# NitroxAnalyzer_v2.net
KiCad netlist of a schematic drawn in EAGLE
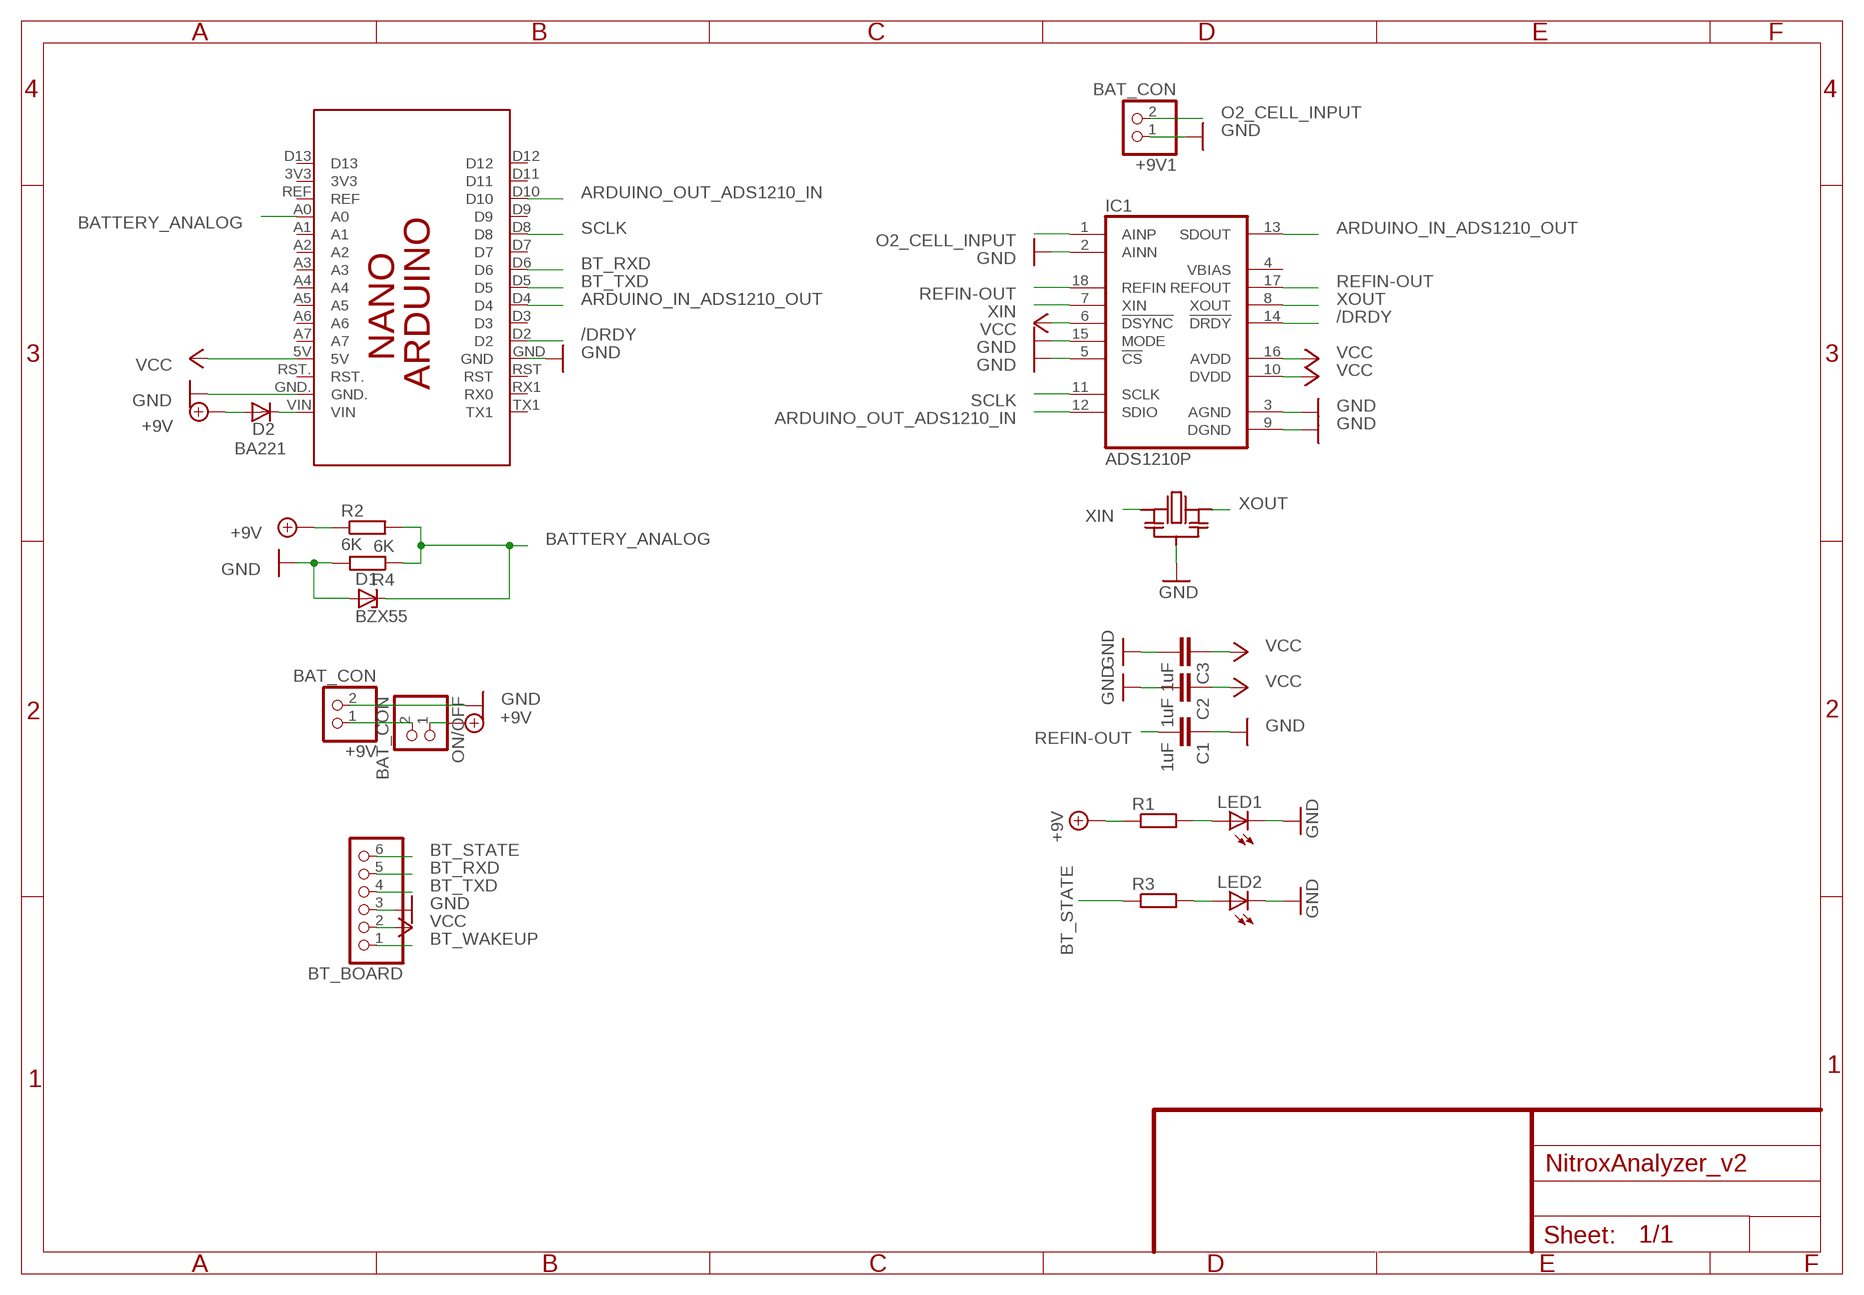
[diagram p0: schematic, sheet 1]

(export (version "E")
  (design (tool "Eeschema 10.0.6"))
  (components
    (comp (ref "+9V")
      (value "BAT_CON")
      (footprint "eagle-import:1X02")
      (libsource (lib "eagle-import") (part "PINHD-1X2"))
    )
    (comp (ref "+9V1")
      (value "BAT_CON")
      (footprint "eagle-import:1X02")
      (libsource (lib "eagle-import") (part "PINHD-1X2"))
    )
    (comp (ref "BT_BOARD")
      (value "PINHD-1X6")
      (footprint "eagle-import:1X06")
      (libsource (lib "eagle-import") (part "PINHD-1X6"))
    )
    (comp (ref "C1")
      (value "1uF")
      (footprint "eagle-import:C1206")
      (libsource (lib "eagle-import") (part "C-EUC1206"))
    )
    (comp (ref "C2")
      (value "1uF")
      (footprint "eagle-import:C1206")
      (libsource (lib "eagle-import") (part "C-EUC1206"))
    )
    (comp (ref "C3")
      (value "1uF")
      (footprint "eagle-import:C1206")
      (libsource (lib "eagle-import") (part "C-EUC1206"))
    )
    (comp (ref "D1")
      (value "BZX55")
      (footprint "eagle-import:DO35Z10")
      (libsource (lib "eagle-import") (part "BZX55"))
    )
    (comp (ref "D2")
      (value "BA221")
      (footprint "eagle-import:DO35-10")
      (libsource (lib "eagle-import") (part "BA221"))
    )
    (comp (ref "IC1")
      (value "ADS1210P")
      (footprint "eagle-import:DIL18")
      (libsource (lib "eagle-import") (part "ADS1210P"))
    )
    (comp (ref "LED1")
      (value "LED3MM")
      (footprint "eagle-import:LED3MM")
      (libsource (lib "eagle-import") (part "LED3MM"))
    )
    (comp (ref "LED2")
      (value "LED3MM")
      (footprint "eagle-import:LED3MM")
      (libsource (lib "eagle-import") (part "LED3MM"))
    )
    (comp (ref "ON/OFF")
      (value "BAT_CON")
      (footprint "eagle-import:1X02")
      (libsource (lib "eagle-import") (part "PINHD-1X2"))
    )
    (comp (ref "PCB1")
      (value "ARDUINO_NANO_SOCKET")
      (footprint "eagle-import:ARDUINO_NANO_SOCKET")
      (libsource (lib "eagle-import") (part "ARDUINO_NANO_SOCKET"))
    )
    (comp (ref "R1")
      (value "R-EU_R1206")
      (footprint "eagle-import:R1206")
      (libsource (lib "eagle-import") (part "R-EU_R1206"))
    )
    (comp (ref "R2")
      (value "6K")
      (footprint "eagle-import:R1206")
      (libsource (lib "eagle-import") (part "R-EU_R1206"))
    )
    (comp (ref "R3")
      (value "R-EU_R1206")
      (footprint "eagle-import:R1206")
      (libsource (lib "eagle-import") (part "R-EU_R1206"))
    )
    (comp (ref "R4")
      (value "6K")
      (footprint "eagle-import:R1206")
      (libsource (lib "eagle-import") (part "R-EU_R1206"))
    )
    (comp (ref "U$2")
      (value "RESONATOR")
      (footprint "eagle-import:RESONATOR")
      (libsource (lib "eagle-import") (part "RESONATOR"))
    )
  )
  (nets
    (net (code "1") (name "+9V") (class "Default")
      (node (ref "D2") (pin "A") (pinfunction "A_A") (pintype "passive"))
      (node (ref "ON/OFF") (pin "1") (pinfunction "1_1") (pintype "passive"))
      (node (ref "R1") (pin "1") (pinfunction "1_1") (pintype "passive"))
      (node (ref "R2") (pin "1") (pinfunction "1_1") (pintype "passive"))
    )
    (net (code "2") (name "/ARDUINO_IN_ADS1210_OUT") (class "Default")
      (node (ref "IC1") (pin "13") (pinfunction "SDOUT_13") (pintype "output"))
      (node (ref "PCB1") (pin "D4") (pinfunction "D4_D4") (pintype "bidirectional"))
    )
    (net (code "3") (name "/ARDUINO_OUT_ADS1210_IN") (class "Default")
      (node (ref "IC1") (pin "12") (pinfunction "SDIO_12") (pintype "bidirectional"))
      (node (ref "PCB1") (pin "D10") (pinfunction "D10_D10") (pintype "bidirectional"))
    )
    (net (code "4") (name "/BATTERY_ANALOG") (class "Default")
      (node (ref "D1") (pin "C") (pinfunction "C_C") (pintype "passive"))
      (node (ref "PCB1") (pin "A0") (pinfunction "A0_A0") (pintype "bidirectional"))
      (node (ref "R2") (pin "2") (pinfunction "2_2") (pintype "passive"))
      (node (ref "R4") (pin "1") (pinfunction "1_1") (pintype "passive"))
    )
    (net (code "5") (name "/BT_RXD") (class "Default")
      (node (ref "BT_BOARD") (pin "5") (pinfunction "5_5") (pintype "passive"))
      (node (ref "PCB1") (pin "D6") (pinfunction "D6_D6") (pintype "bidirectional"))
    )
    (net (code "6") (name "/BT_STATE") (class "Default")
      (node (ref "BT_BOARD") (pin "6") (pinfunction "6_6") (pintype "passive"))
      (node (ref "R3") (pin "1") (pinfunction "1_1") (pintype "passive"))
    )
    (net (code "7") (name "/BT_TXD") (class "Default")
      (node (ref "BT_BOARD") (pin "4") (pinfunction "4_4") (pintype "passive"))
      (node (ref "PCB1") (pin "D5") (pinfunction "D5_D5") (pintype "bidirectional"))
    )
    (net (code "8") (name "/BT_WAKEUP") (class "Default")
      (node (ref "BT_BOARD") (pin "1") (pinfunction "1_1") (pintype "passive"))
    )
    (net (code "9") (name "/O2_CELL_INPUT") (class "Default")
      (node (ref "+9V1") (pin "2") (pinfunction "2_2") (pintype "passive"))
      (node (ref "IC1") (pin "1") (pinfunction "AINP_1") (pintype "input"))
    )
    (net (code "10") (name "/REFIN-OUT") (class "Default")
      (node (ref "C1") (pin "2") (pinfunction "2_2") (pintype "passive"))
      (node (ref "IC1") (pin "17") (pinfunction "REFOUT_17") (pintype "output"))
      (node (ref "IC1") (pin "18") (pinfunction "REFIN_18") (pintype "input"))
    )
    (net (code "11") (name "/SCLK") (class "Default")
      (node (ref "IC1") (pin "11") (pinfunction "SCLK_11") (pintype "bidirectional"))
      (node (ref "PCB1") (pin "D8") (pinfunction "D8_D8") (pintype "bidirectional"))
    )
    (net (code "12") (name "/XIN") (class "Default")
      (node (ref "IC1") (pin "7") (pinfunction "XIN_7") (pintype "input"))
      (node (ref "U$2") (pin "P$1") (pinfunction "IN_P$1") (pintype "bidirectional"))
    )
    (net (code "13") (name "/XOUT") (class "Default")
      (node (ref "IC1") (pin "8") (pinfunction "XOUT_8") (pintype "output"))
      (node (ref "U$2") (pin "P$3") (pinfunction "OUT_P$3") (pintype "bidirectional"))
    )
    (net (code "14") (name "/{slash}DRDY") (class "Default")
      (node (ref "IC1") (pin "14") (pinfunction "~{DRDY}_14") (pintype "output"))
      (node (ref "PCB1") (pin "D2") (pinfunction "D2_D2") (pintype "bidirectional"))
    )
    (net (code "15") (name "GND") (class "Default")
      (node (ref "+9V") (pin "2") (pinfunction "2_2") (pintype "passive"))
      (node (ref "+9V1") (pin "1") (pinfunction "1_1") (pintype "passive"))
      (node (ref "BT_BOARD") (pin "3") (pinfunction "3_3") (pintype "passive"))
      (node (ref "C1") (pin "1") (pinfunction "1_1") (pintype "passive"))
      (node (ref "C2") (pin "2") (pinfunction "2_2") (pintype "passive"))
      (node (ref "C3") (pin "2") (pinfunction "2_2") (pintype "passive"))
      (node (ref "D1") (pin "A") (pinfunction "A_A") (pintype "passive"))
      (node (ref "IC1") (pin "15") (pinfunction "MODE_15") (pintype "input"))
      (node (ref "IC1") (pin "2") (pinfunction "AINN_2") (pintype "input"))
      (node (ref "IC1") (pin "3") (pinfunction "AGND_3") (pintype "power_in"))
      (node (ref "IC1") (pin "5") (pinfunction "~{CS}_5") (pintype "input"))
      (node (ref "IC1") (pin "9") (pinfunction "DGND_9") (pintype "power_in"))
      (node (ref "LED1") (pin "K") (pinfunction "C_K") (pintype "passive"))
      (node (ref "LED2") (pin "K") (pinfunction "C_K") (pintype "passive"))
      (node (ref "PCB1") (pin "GND") (pinfunction "GND_GND") (pintype "bidirectional"))
      (node (ref "PCB1") (pin "GND.") (pinfunction "GND._GND.") (pintype "bidirectional"))
      (node (ref "R4") (pin "2") (pinfunction "2_2") (pintype "passive"))
      (node (ref "U$2") (pin "P$2") (pinfunction "GND_P$2") (pintype "bidirectional"))
    )
    (net (code "16") (name "Net-(+9V-Pad1)") (class "Default")
      (node (ref "+9V") (pin "1") (pinfunction "1_1") (pintype "passive"))
      (node (ref "ON/OFF") (pin "2") (pinfunction "2_2") (pintype "passive"))
    )
    (net (code "17") (name "Net-(D2-PadC)") (class "Default")
      (node (ref "D2") (pin "C") (pinfunction "C_C") (pintype "passive"))
      (node (ref "PCB1") (pin "VIN") (pinfunction "VIN_VIN") (pintype "bidirectional"))
    )
    (net (code "18") (name "Net-(LED1-PadA)") (class "Default")
      (node (ref "LED1") (pin "A") (pinfunction "A_A") (pintype "passive"))
      (node (ref "R1") (pin "2") (pinfunction "2_2") (pintype "passive"))
    )
    (net (code "19") (name "Net-(LED2-PadA)") (class "Default")
      (node (ref "LED2") (pin "A") (pinfunction "A_A") (pintype "passive"))
      (node (ref "R3") (pin "2") (pinfunction "2_2") (pintype "passive"))
    )
    (net (code "20") (name "VCC") (class "Default")
      (node (ref "BT_BOARD") (pin "2") (pinfunction "2_2") (pintype "passive"))
      (node (ref "C2") (pin "1") (pinfunction "1_1") (pintype "passive"))
      (node (ref "C3") (pin "1") (pinfunction "1_1") (pintype "passive"))
      (node (ref "IC1") (pin "10") (pinfunction "DVDD_10") (pintype "power_in"))
      (node (ref "IC1") (pin "16") (pinfunction "AVDD_16") (pintype "power_in"))
      (node (ref "IC1") (pin "6") (pinfunction "~{DSYNC}_6") (pintype "input"))
      (node (ref "PCB1") (pin "5V") (pinfunction "5V_5V") (pintype "bidirectional"))
    )
    (net (code "21") (name "unconnected-(IC1-VBIAS-Pad4)") (class "Default")
      (node (ref "IC1") (pin "4") (pinfunction "VBIAS_4") (pintype "output"))
    )
    (net (code "22") (name "unconnected-(PCB1-Pad3V3)") (class "Default")
      (node (ref "PCB1") (pin "3V3") (pinfunction "3V3_3V3") (pintype "bidirectional"))
    )
    (net (code "23") (name "unconnected-(PCB1-PadA1)") (class "Default")
      (node (ref "PCB1") (pin "A1") (pinfunction "A1_A1") (pintype "bidirectional"))
    )
    (net (code "24") (name "unconnected-(PCB1-PadA2)") (class "Default")
      (node (ref "PCB1") (pin "A2") (pinfunction "A2_A2") (pintype "bidirectional"))
    )
    (net (code "25") (name "unconnected-(PCB1-PadA3)") (class "Default")
      (node (ref "PCB1") (pin "A3") (pinfunction "A3_A3") (pintype "bidirectional"))
    )
    (net (code "26") (name "unconnected-(PCB1-PadA4)") (class "Default")
      (node (ref "PCB1") (pin "A4") (pinfunction "A4_A4") (pintype "bidirectional"))
    )
    (net (code "27") (name "unconnected-(PCB1-PadA5)") (class "Default")
      (node (ref "PCB1") (pin "A5") (pinfunction "A5_A5") (pintype "bidirectional"))
    )
    (net (code "28") (name "unconnected-(PCB1-PadA6)") (class "Default")
      (node (ref "PCB1") (pin "A6") (pinfunction "A6_A6") (pintype "bidirectional"))
    )
    (net (code "29") (name "unconnected-(PCB1-PadA7)") (class "Default")
      (node (ref "PCB1") (pin "A7") (pinfunction "A7_A7") (pintype "bidirectional"))
    )
    (net (code "30") (name "unconnected-(PCB1-PadD3)") (class "Default")
      (node (ref "PCB1") (pin "D3") (pinfunction "D3_D3") (pintype "bidirectional"))
    )
    (net (code "31") (name "unconnected-(PCB1-PadD7)") (class "Default")
      (node (ref "PCB1") (pin "D7") (pinfunction "D7_D7") (pintype "bidirectional"))
    )
    (net (code "32") (name "unconnected-(PCB1-PadD9)") (class "Default")
      (node (ref "PCB1") (pin "D9") (pinfunction "D9_D9") (pintype "bidirectional"))
    )
    (net (code "33") (name "unconnected-(PCB1-PadD11)") (class "Default")
      (node (ref "PCB1") (pin "D11") (pinfunction "D11_D11") (pintype "bidirectional"))
    )
    (net (code "34") (name "unconnected-(PCB1-PadD12)") (class "Default")
      (node (ref "PCB1") (pin "D12") (pinfunction "D12_D12") (pintype "bidirectional"))
    )
    (net (code "35") (name "unconnected-(PCB1-PadD13)") (class "Default")
      (node (ref "PCB1") (pin "D13") (pinfunction "D13_D13") (pintype "bidirectional"))
    )
    (net (code "36") (name "unconnected-(PCB1-PadREF)") (class "Default")
      (node (ref "PCB1") (pin "REF") (pinfunction "REF_REF") (pintype "bidirectional"))
    )
    (net (code "37") (name "unconnected-(PCB1-PadRST)") (class "Default")
      (node (ref "PCB1") (pin "RST") (pinfunction "RST_RST") (pintype "bidirectional"))
    )
    (net (code "38") (name "unconnected-(PCB1-PadRST.)") (class "Default")
      (node (ref "PCB1") (pin "RST.") (pinfunction "RST._RST.") (pintype "bidirectional"))
    )
    (net (code "39") (name "unconnected-(PCB1-PadTX1)") (class "Default")
      (node (ref "PCB1") (pin "TX1") (pinfunction "TX1_TX1") (pintype "bidirectional"))
    )
    (net (code "40") (name "unconnected-(PCB1-RX0-PadRX1)") (class "Default")
      (node (ref "PCB1") (pin "RX1") (pinfunction "RX0_RX1") (pintype "bidirectional"))
    )
  )
)
